# Power_Supply_Flat_Rev_C.net
KiCad netlist of a schematic drawn in EAGLE
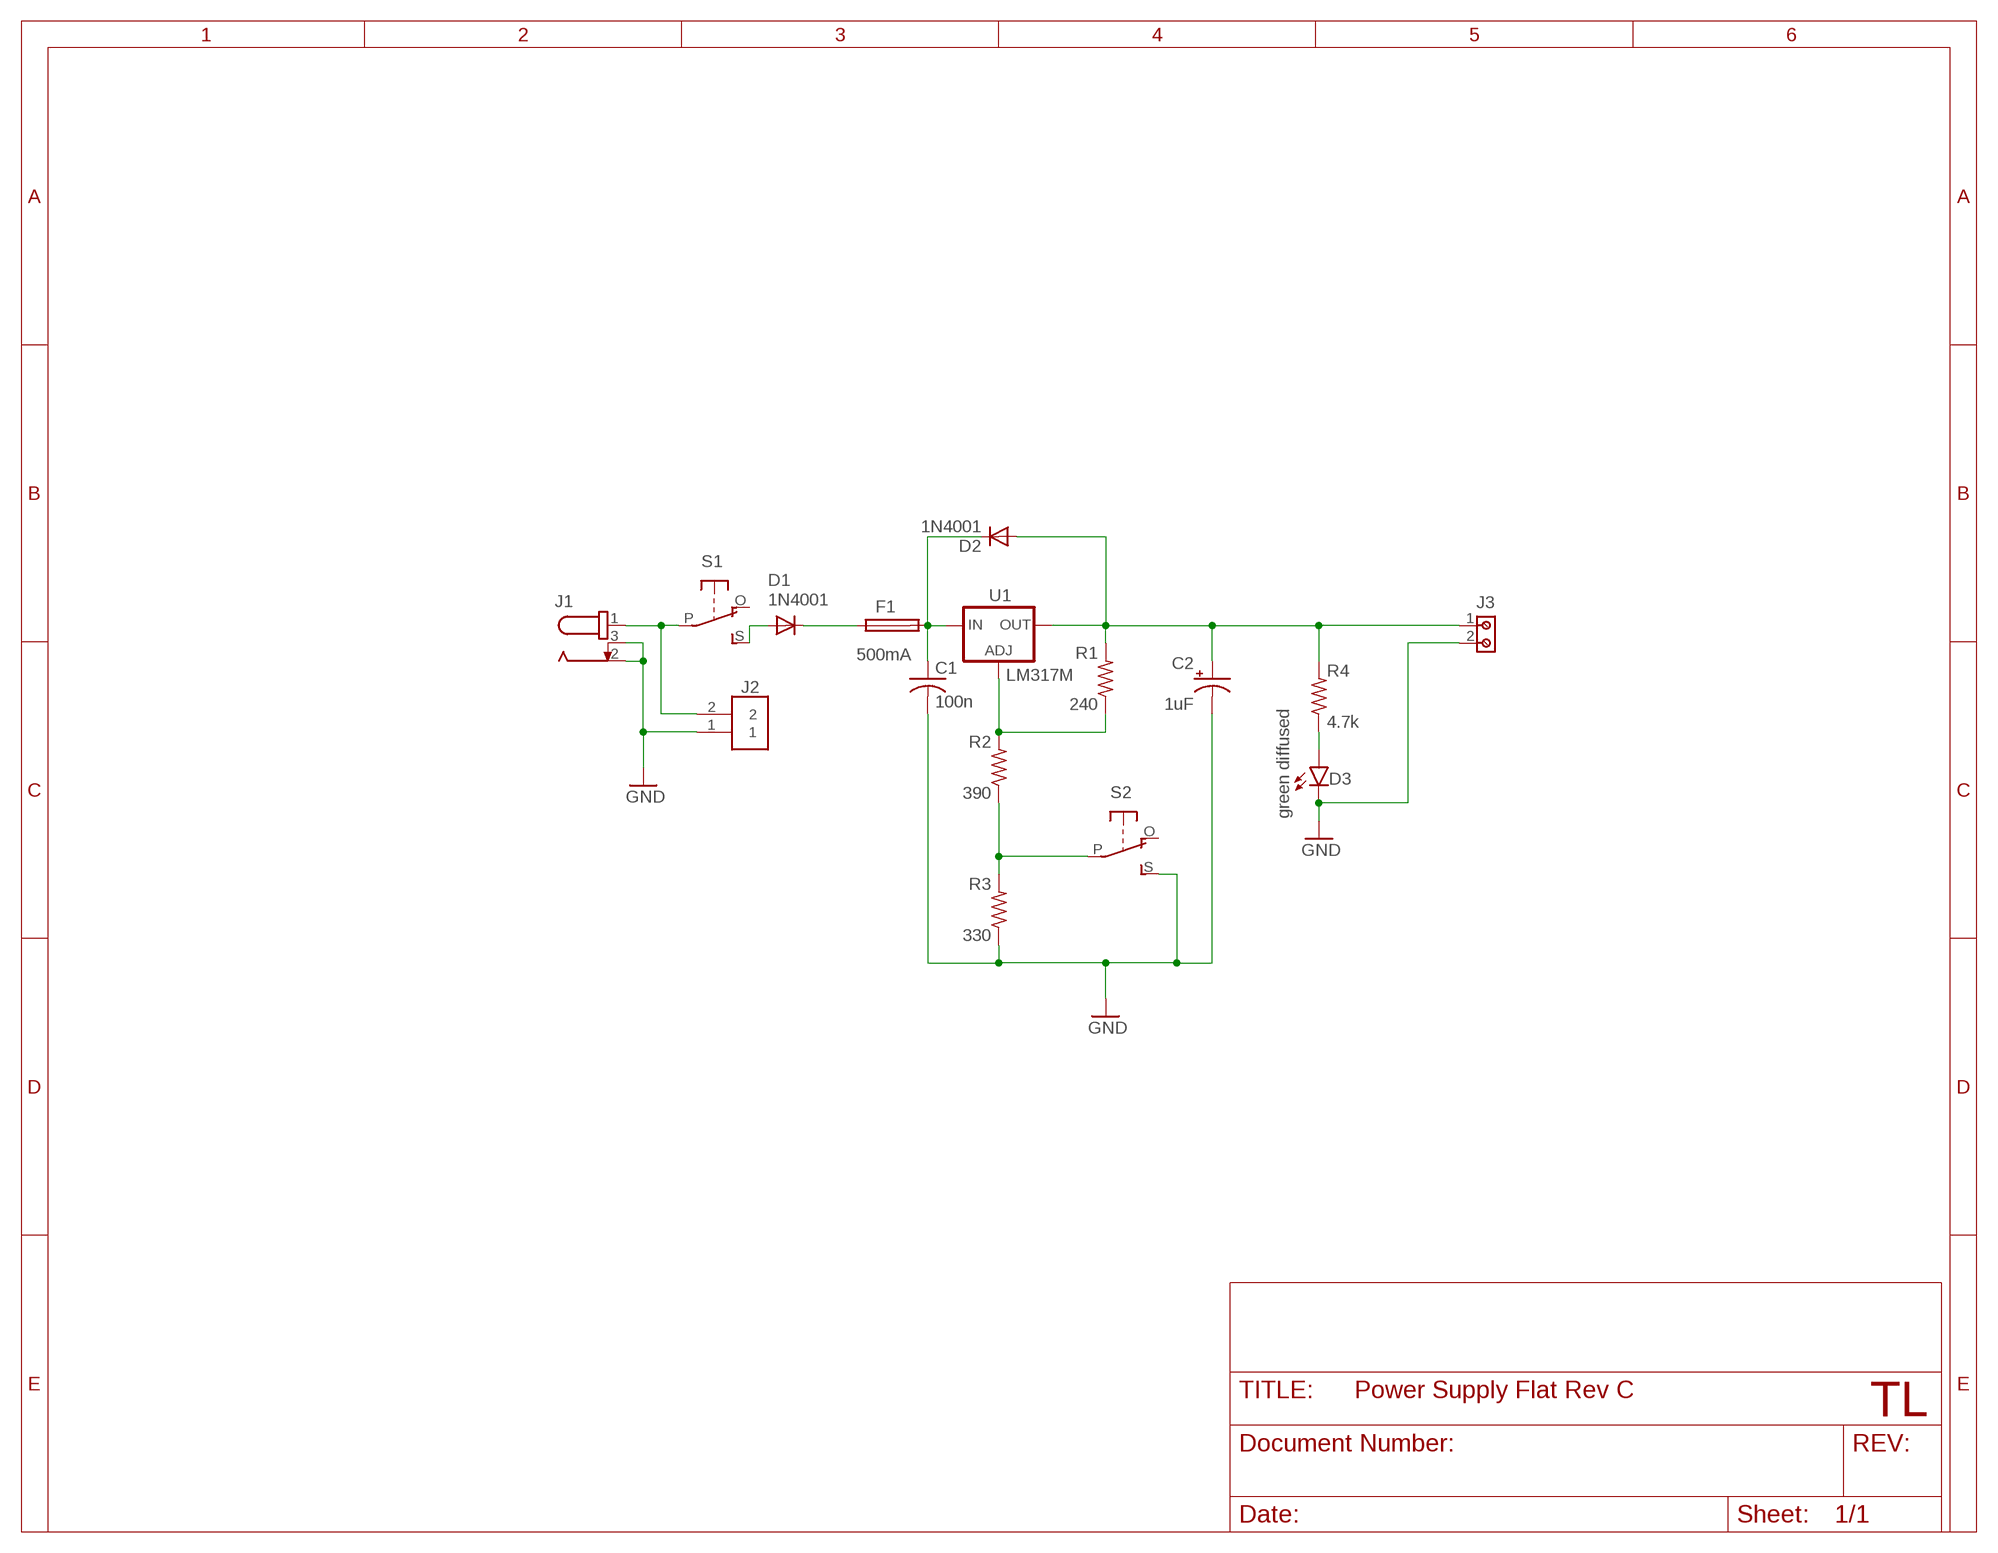
[diagram p0: schematic, sheet 1]

(export (version "E")
  (design (tool "Eeschema 10.0.6"))
  (components
    (comp (ref "C1")
      (value "100n")
      (footprint "eagle-import:C050-024X044")
      (libsource (lib "eagle-import") (part "CAPACITOR-CERAMIC"))
    )
    (comp (ref "C2")
      (value "1uF")
      (footprint "eagle-import:E2-4")
      (libsource (lib "eagle-import") (part "E-CAPACITOR2-4"))
    )
    (comp (ref "D1")
      (value "1N4001")
      (footprint "eagle-import:DO41-10")
      (libsource (lib "eagle-import") (part "1N4000"))
    )
    (comp (ref "D2")
      (value "1N4001")
      (footprint "eagle-import:DO41-10")
      (libsource (lib "eagle-import") (part "1N4000"))
    )
    (comp (ref "D3")
      (value "green diffused")
      (footprint "eagle-import:LED5MM")
      (libsource (lib "eagle-import") (part "LED"))
    )
    (comp (ref "F1")
      (value "500mA")
      (footprint "eagle-import:PTC-FUSE")
      (libsource (lib "eagle-import") (part "PTC-FUSE"))
    )
    (comp (ref "J1")
      (value "694106301002")
      (footprint "eagle-import:694106301002")
      (fields
        (field (name "DIGIKEY_PART_NUMBER") "732-5930-ND")
        (field (name "MANUFACTURER") "Wurth Electronics Inc.")
        (field (name "CREATED_BY") "PCBLayout.com")
      )
      (libsource (lib "eagle-import") (part "694106301002"))
    )
    (comp (ref "J2")
      (value "61300211121")
      (footprint "eagle-import:61300211121")
      (fields
        (field (name "DIGI_KEY_PART_NUMBER") "732-5315-ND")
        (field (name "MANUFACTURER") "Wurth Electronics Inc.")
        (field (name "CREATED_BY") "PCBLayout.com")
      )
      (libsource (lib "eagle-import") (part "61300211121"))
    )
    (comp (ref "J3")
      (value "691214110002")
      (footprint "eagle-import:691214110002")
      (libsource (lib "eagle-import") (part "691214110002"))
    )
    (comp (ref "R1")
      (value "240")
      (footprint "eagle-import:0207_10")
      (libsource (lib "eagle-import") (part "RESISTOR"))
    )
    (comp (ref "R2")
      (value "390")
      (footprint "eagle-import:0207_10")
      (libsource (lib "eagle-import") (part "RESISTOR"))
    )
    (comp (ref "R3")
      (value "330")
      (footprint "eagle-import:0207_10")
      (libsource (lib "eagle-import") (part "RESISTOR"))
    )
    (comp (ref "R4")
      (value "4.7k")
      (footprint "eagle-import:0207_10")
      (libsource (lib "eagle-import") (part "RESISTOR"))
    )
    (comp (ref "S1")
      (value "SLIDE-SWITCHSIDE")
      (footprint "eagle-import:EG1270-90")
      (libsource (lib "eagle-import") (part "SLIDE-SWITCHSIDE"))
    )
    (comp (ref "S2")
      (value "SLIDE-SWITCHSIDE")
      (footprint "eagle-import:EG1270-90")
      (libsource (lib "eagle-import") (part "SLIDE-SWITCHSIDE"))
    )
    (comp (ref "U1")
      (value "LM317BENT")
      (footprint "eagle-import:T03B")
      (fields (field (name "PARTNUMBER") "LM317M"))
      (libsource (lib "eagle-import") (part "LM317BENT"))
    )
  )
  (nets
    (net (code "1") (name "GND") (class "Default")
      (node (ref "C1") (pin "2") (pinfunction "2_2") (pintype "passive"))
      (node (ref "C2") (pin "-") (pinfunction "-_-") (pintype "passive"))
      (node (ref "D3") (pin "K") (pinfunction "C_K") (pintype "passive"))
      (node (ref "J1") (pin "2") (pinfunction "2_2") (pintype "passive"))
      (node (ref "J1") (pin "3") (pinfunction "3_3") (pintype "passive"))
      (node (ref "J2") (pin "1") (pinfunction "1_1") (pintype "passive"))
      (node (ref "J3") (pin "2") (pinfunction "2_2") (pintype "passive"))
      (node (ref "R3") (pin "1") (pinfunction "1_1") (pintype "passive"))
      (node (ref "S2") (pin "S") (pinfunction "S_S") (pintype "passive"))
    )
    (net (code "2") (name "Net-(D1-PadA)") (class "Default")
      (node (ref "D1") (pin "A") (pinfunction "A_A") (pintype "passive"))
      (node (ref "S1") (pin "S") (pinfunction "S_S") (pintype "passive"))
    )
    (net (code "3") (name "Net-(D1-PadC)") (class "Default")
      (node (ref "D1") (pin "C") (pinfunction "C_C") (pintype "passive"))
      (node (ref "F1") (pin "1") (pinfunction "1_1") (pintype "passive"))
    )
    (net (code "4") (name "Net-(D3-PadA)") (class "Default")
      (node (ref "D3") (pin "A") (pinfunction "A_A") (pintype "passive"))
      (node (ref "R4") (pin "1") (pinfunction "1_1") (pintype "passive"))
    )
    (net (code "5") (name "Net-(J1-Pad1)") (class "Default")
      (node (ref "J1") (pin "1") (pinfunction "1_1") (pintype "passive"))
      (node (ref "J2") (pin "2") (pinfunction "2_2") (pintype "passive"))
      (node (ref "S1") (pin "P") (pinfunction "P_P") (pintype "passive"))
    )
    (net (code "6") (name "Net-(R2-Pad1)") (class "Default")
      (node (ref "R2") (pin "1") (pinfunction "1_1") (pintype "passive"))
      (node (ref "R3") (pin "2") (pinfunction "2_2") (pintype "passive"))
      (node (ref "S2") (pin "P") (pinfunction "P_P") (pintype "passive"))
    )
    (net (code "7") (name "Net-(U1-ADJ)") (class "Default")
      (node (ref "R1") (pin "1") (pinfunction "1_1") (pintype "passive"))
      (node (ref "R2") (pin "2") (pinfunction "2_2") (pintype "passive"))
      (node (ref "U1") (pin "1") (pinfunction "ADJ_1") (pintype "input"))
    )
    (net (code "8") (name "Net-(U1-IN)") (class "Default")
      (node (ref "C1") (pin "1") (pinfunction "1_1") (pintype "passive"))
      (node (ref "D2") (pin "C") (pinfunction "C_C") (pintype "passive"))
      (node (ref "F1") (pin "2") (pinfunction "2_2") (pintype "passive"))
      (node (ref "U1") (pin "3") (pinfunction "IN_3") (pintype "input"))
    )
    (net (code "9") (name "Net-(U1-OUT)") (class "Default")
      (node (ref "C2") (pin "+") (pinfunction "+_+") (pintype "passive"))
      (node (ref "D2") (pin "A") (pinfunction "A_A") (pintype "passive"))
      (node (ref "J3") (pin "1") (pinfunction "1_1") (pintype "passive"))
      (node (ref "R1") (pin "2") (pinfunction "2_2") (pintype "passive"))
      (node (ref "R4") (pin "2") (pinfunction "2_2") (pintype "passive"))
      (node (ref "U1") (pin "2") (pinfunction "OUT_2") (pintype "passive"))
    )
    (net (code "10") (name "unconnected-(S1-PadO)") (class "Default")
      (node (ref "S1") (pin "O") (pinfunction "O_O") (pintype "passive"))
    )
    (net (code "11") (name "unconnected-(S2-PadO)") (class "Default")
      (node (ref "S2") (pin "O") (pinfunction "O_O") (pintype "passive"))
    )
  )
)
